# programmer.net
KiCad netlist of a schematic drawn in EAGLE
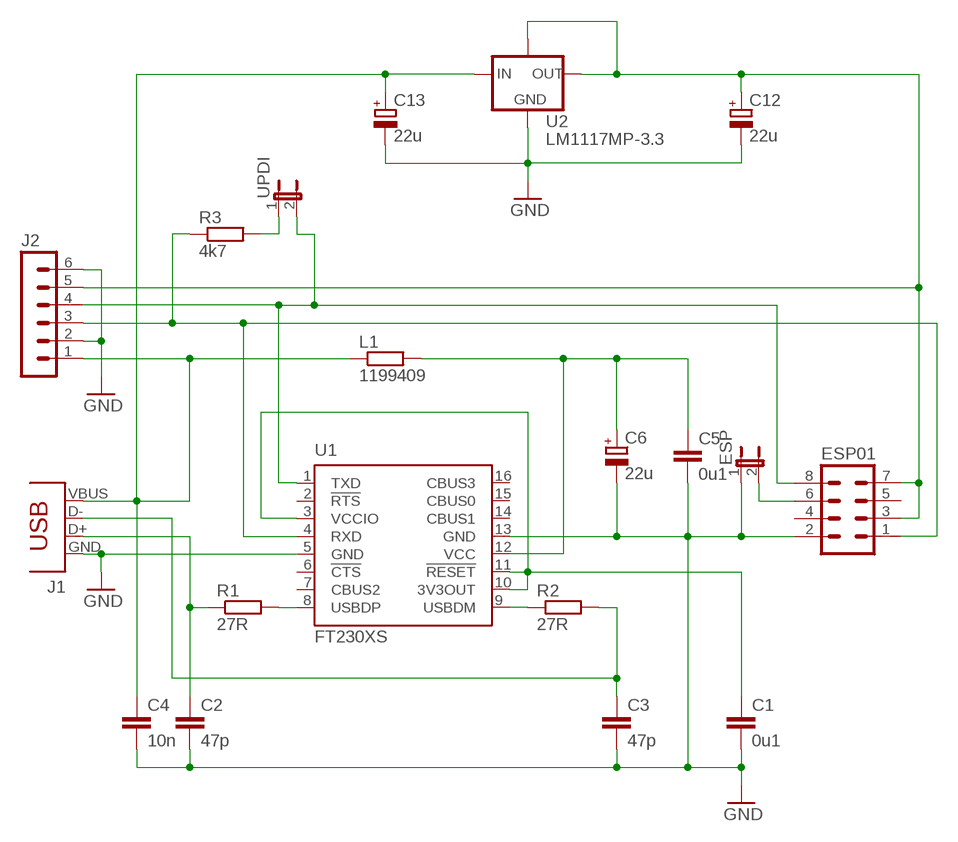
[diagram p0: schematic, sheet 1]

(export (version "E")
  (design (tool "Eeschema 10.0.6"))
  (components
    (comp (ref "C1")
      (value "0u1")
      (footprint "eagle-import:C0805")
      (libsource (lib "eagle-import") (part "C-EUC0805"))
    )
    (comp (ref "C2")
      (value "47p")
      (footprint "eagle-import:C0805")
      (libsource (lib "eagle-import") (part "C-EUC0805"))
    )
    (comp (ref "C3")
      (value "47p")
      (footprint "eagle-import:C0805")
      (libsource (lib "eagle-import") (part "C-EUC0805"))
    )
    (comp (ref "C4")
      (value "10n")
      (footprint "eagle-import:C0805")
      (libsource (lib "eagle-import") (part "C-EUC0805"))
    )
    (comp (ref "C5")
      (value "0u1")
      (footprint "eagle-import:C0805")
      (libsource (lib "eagle-import") (part "C-EUC0805"))
    )
    (comp (ref "C6")
      (value "22u")
      (footprint "eagle-import:E1,8-4")
      (libsource (lib "eagle-import") (part "CPOL-EUE1.8-4"))
    )
    (comp (ref "C12")
      (value "22u")
      (footprint "eagle-import:E1,8-4")
      (libsource (lib "eagle-import") (part "CPOL-EUE1.8-4"))
    )
    (comp (ref "C13")
      (value "22u")
      (footprint "eagle-import:E1,8-4")
      (libsource (lib "eagle-import") (part "CPOL-EUE1.8-4"))
    )
    (comp (ref "ESP")
      (value "JP1E")
      (footprint "eagle-import:JP1")
      (libsource (lib "eagle-import") (part "JP1E"))
    )
    (comp (ref "ESP01")
      (value "MA04-2")
      (footprint "eagle-import:MA04-2")
      (libsource (lib "eagle-import") (part "MA04-2"))
    )
    (comp (ref "J1")
      (value "USB_A_PLUG")
      (footprint "eagle-import:USB_A_PLUG")
      (libsource (lib "eagle-import") (part "USB_A_PLUG"))
    )
    (comp (ref "J2")
      (value "MA06-1")
      (footprint "eagle-import:MA06-1")
      (libsource (lib "eagle-import") (part "MA06-1"))
    )
    (comp (ref "L1")
      (value "1199409")
      (footprint "eagle-import:M0805")
      (libsource (lib "eagle-import") (part "R-EU_M0805"))
    )
    (comp (ref "R1")
      (value "27R")
      (footprint "eagle-import:M0805")
      (libsource (lib "eagle-import") (part "R-EU_M0805"))
    )
    (comp (ref "R2")
      (value "27R")
      (footprint "eagle-import:M0805")
      (libsource (lib "eagle-import") (part "R-EU_M0805"))
    )
    (comp (ref "R3")
      (value "4k7")
      (footprint "eagle-import:0207_10")
      (libsource (lib "eagle-import") (part "R-EU_0207/10"))
    )
    (comp (ref "U1")
      (value "FT230XS")
      (footprint "eagle-import:SSOP16")
      (libsource (lib "eagle-import") (part "FT230XS"))
    )
    (comp (ref "U2")
      (value "LM1117MP-3.3")
      (footprint "eagle-import:SOT230P700X180-4N")
      (libsource (lib "eagle-import") (part "LM1117"))
    )
    (comp (ref "UPDI")
      (value "JP1E")
      (footprint "eagle-import:JP1")
      (libsource (lib "eagle-import") (part "JP1E"))
    )
  )
  (nets
    (net (code "1") (name "GND") (class "Default")
      (node (ref "C1") (pin "2") (pinfunction "2_2") (pintype "passive"))
      (node (ref "C12") (pin "-") (pinfunction "-_-") (pintype "passive"))
      (node (ref "C13") (pin "-") (pinfunction "-_-") (pintype "passive"))
      (node (ref "C2") (pin "2") (pinfunction "2_2") (pintype "passive"))
      (node (ref "C3") (pin "2") (pinfunction "2_2") (pintype "passive"))
      (node (ref "C4") (pin "2") (pinfunction "2_2") (pintype "passive"))
      (node (ref "C5") (pin "2") (pinfunction "2_2") (pintype "passive"))
      (node (ref "C6") (pin "-") (pinfunction "-_-") (pintype "passive"))
      (node (ref "ESP") (pin "1") (pinfunction "1_1") (pintype "passive"))
      (node (ref "ESP01") (pin "2") (pinfunction "2_2") (pintype "passive"))
      (node (ref "J1") (pin "GND") (pinfunction "1_GND") (pintype "passive"))
      (node (ref "J2") (pin "2") (pinfunction "2_2") (pintype "passive"))
      (node (ref "J2") (pin "6") (pinfunction "6_6") (pintype "passive"))
      (node (ref "U1") (pin "13") (pinfunction "GND_13") (pintype "power_in"))
      (node (ref "U1") (pin "5") (pinfunction "GND_5") (pintype "power_in"))
      (node (ref "U2") (pin "1") (pinfunction "GND_1") (pintype "input"))
    )
    (net (code "2") (name "Net-(ESP-Pad2)") (class "Default")
      (node (ref "ESP") (pin "2") (pinfunction "2_2") (pintype "passive"))
      (node (ref "ESP01") (pin "6") (pinfunction "6_6") (pintype "passive"))
    )
    (net (code "3") (name "Net-(J1-2)") (class "Default")
      (node (ref "C2") (pin "1") (pinfunction "1_1") (pintype "passive"))
      (node (ref "J1") (pin "D+") (pinfunction "2_D+") (pintype "passive"))
      (node (ref "R1") (pin "1") (pinfunction "1_1") (pintype "passive"))
    )
    (net (code "4") (name "Net-(J1-3)") (class "Default")
      (node (ref "C3") (pin "1") (pinfunction "1_1") (pintype "passive"))
      (node (ref "J1") (pin "D-") (pinfunction "3_D-") (pintype "passive"))
      (node (ref "R2") (pin "2") (pinfunction "2_2") (pintype "passive"))
    )
    (net (code "5") (name "Net-(J1-4)") (class "Default")
      (node (ref "C13") (pin "+") (pinfunction "+_+") (pintype "passive"))
      (node (ref "C4") (pin "1") (pinfunction "1_1") (pintype "passive"))
      (node (ref "J1") (pin "VBUS") (pinfunction "4_VBUS") (pintype "passive"))
      (node (ref "J2") (pin "1") (pinfunction "1_1") (pintype "passive"))
      (node (ref "L1") (pin "1") (pinfunction "1_1") (pintype "passive"))
      (node (ref "U2") (pin "3") (pinfunction "IN_3") (pintype "input"))
    )
    (net (code "6") (name "Net-(R3-Pad2)") (class "Default")
      (node (ref "R3") (pin "2") (pinfunction "2_2") (pintype "passive"))
      (node (ref "UPDI") (pin "1") (pinfunction "1_1") (pintype "passive"))
    )
    (net (code "7") (name "Net-(U1-3V3OUT)") (class "Default")
      (node (ref "C1") (pin "1") (pinfunction "1_1") (pintype "passive"))
      (node (ref "U1") (pin "10") (pinfunction "3V3OUT_10") (pintype "output"))
      (node (ref "U1") (pin "11") (pinfunction "~{RESET}_11") (pintype "input"))
      (node (ref "U1") (pin "3") (pinfunction "VCCIO_3") (pintype "power_in"))
    )
    (net (code "8") (name "Net-(U1-RXD)") (class "Default")
      (node (ref "ESP01") (pin "1") (pinfunction "1_1") (pintype "passive"))
      (node (ref "J2") (pin "3") (pinfunction "3_3") (pintype "passive"))
      (node (ref "R3") (pin "1") (pinfunction "1_1") (pintype "passive"))
      (node (ref "U1") (pin "4") (pinfunction "RXD_4") (pintype "input"))
    )
    (net (code "9") (name "Net-(U1-TXD)") (class "Default")
      (node (ref "ESP01") (pin "8") (pinfunction "8_8") (pintype "passive"))
      (node (ref "J2") (pin "4") (pinfunction "4_4") (pintype "passive"))
      (node (ref "U1") (pin "1") (pinfunction "TXD_1") (pintype "output"))
      (node (ref "UPDI") (pin "2") (pinfunction "2_2") (pintype "passive"))
    )
    (net (code "10") (name "Net-(U1-USBDM)") (class "Default")
      (node (ref "R2") (pin "1") (pinfunction "1_1") (pintype "passive"))
      (node (ref "U1") (pin "9") (pinfunction "USBDM_9") (pintype "input"))
    )
    (net (code "11") (name "Net-(U1-USBDP)") (class "Default")
      (node (ref "R1") (pin "2") (pinfunction "2_2") (pintype "passive"))
      (node (ref "U1") (pin "8") (pinfunction "USBDP_8") (pintype "input"))
    )
    (net (code "12") (name "Net-(U1-VCC)") (class "Default")
      (node (ref "C5") (pin "1") (pinfunction "1_1") (pintype "passive"))
      (node (ref "C6") (pin "+") (pinfunction "+_+") (pintype "passive"))
      (node (ref "L1") (pin "2") (pinfunction "2_2") (pintype "passive"))
      (node (ref "U1") (pin "12") (pinfunction "VCC_12") (pintype "power_in"))
    )
    (net (code "13") (name "Net-(U2-OUT)") (class "Default")
      (node (ref "C12") (pin "+") (pinfunction "+_+") (pintype "passive"))
      (node (ref "ESP01") (pin "3") (pinfunction "3_3") (pintype "passive"))
      (node (ref "ESP01") (pin "7") (pinfunction "7_7") (pintype "passive"))
      (node (ref "J2") (pin "5") (pinfunction "5_5") (pintype "passive"))
      (node (ref "U2") (pin "2") (pinfunction "OUT_2") (pintype "passive"))
      (node (ref "U2") (pin "4") (pinfunction "TAB_4") (pintype "passive"))
    )
    (net (code "14") (name "unconnected-(ESP01-Pad4)") (class "Default")
      (node (ref "ESP01") (pin "4") (pinfunction "4_4") (pintype "passive"))
    )
    (net (code "15") (name "unconnected-(ESP01-Pad5)") (class "Default")
      (node (ref "ESP01") (pin "5") (pinfunction "5_5") (pintype "passive"))
    )
    (net (code "16") (name "unconnected-(U1-CBUS0-Pad15)") (class "Default")
      (node (ref "U1") (pin "15") (pinfunction "CBUS0_15") (pintype "bidirectional"))
    )
    (net (code "17") (name "unconnected-(U1-CBUS1-Pad14)") (class "Default")
      (node (ref "U1") (pin "14") (pinfunction "CBUS1_14") (pintype "bidirectional"))
    )
    (net (code "18") (name "unconnected-(U1-CBUS2-Pad7)") (class "Default")
      (node (ref "U1") (pin "7") (pinfunction "CBUS2_7") (pintype "bidirectional"))
    )
    (net (code "19") (name "unconnected-(U1-CBUS3-Pad16)") (class "Default")
      (node (ref "U1") (pin "16") (pinfunction "CBUS3_16") (pintype "bidirectional"))
    )
    (net (code "20") (name "unconnected-(U1-~{CTS}-Pad6)") (class "Default")
      (node (ref "U1") (pin "6") (pinfunction "~{CTS}_6") (pintype "input"))
    )
    (net (code "21") (name "unconnected-(U1-~{RTS}-Pad2)") (class "Default")
      (node (ref "U1") (pin "2") (pinfunction "~{RTS}_2") (pintype "output"))
    )
  )
)
